# GPM8F3496A.net
KiCad netlist of a schematic drawn in Altium Designer
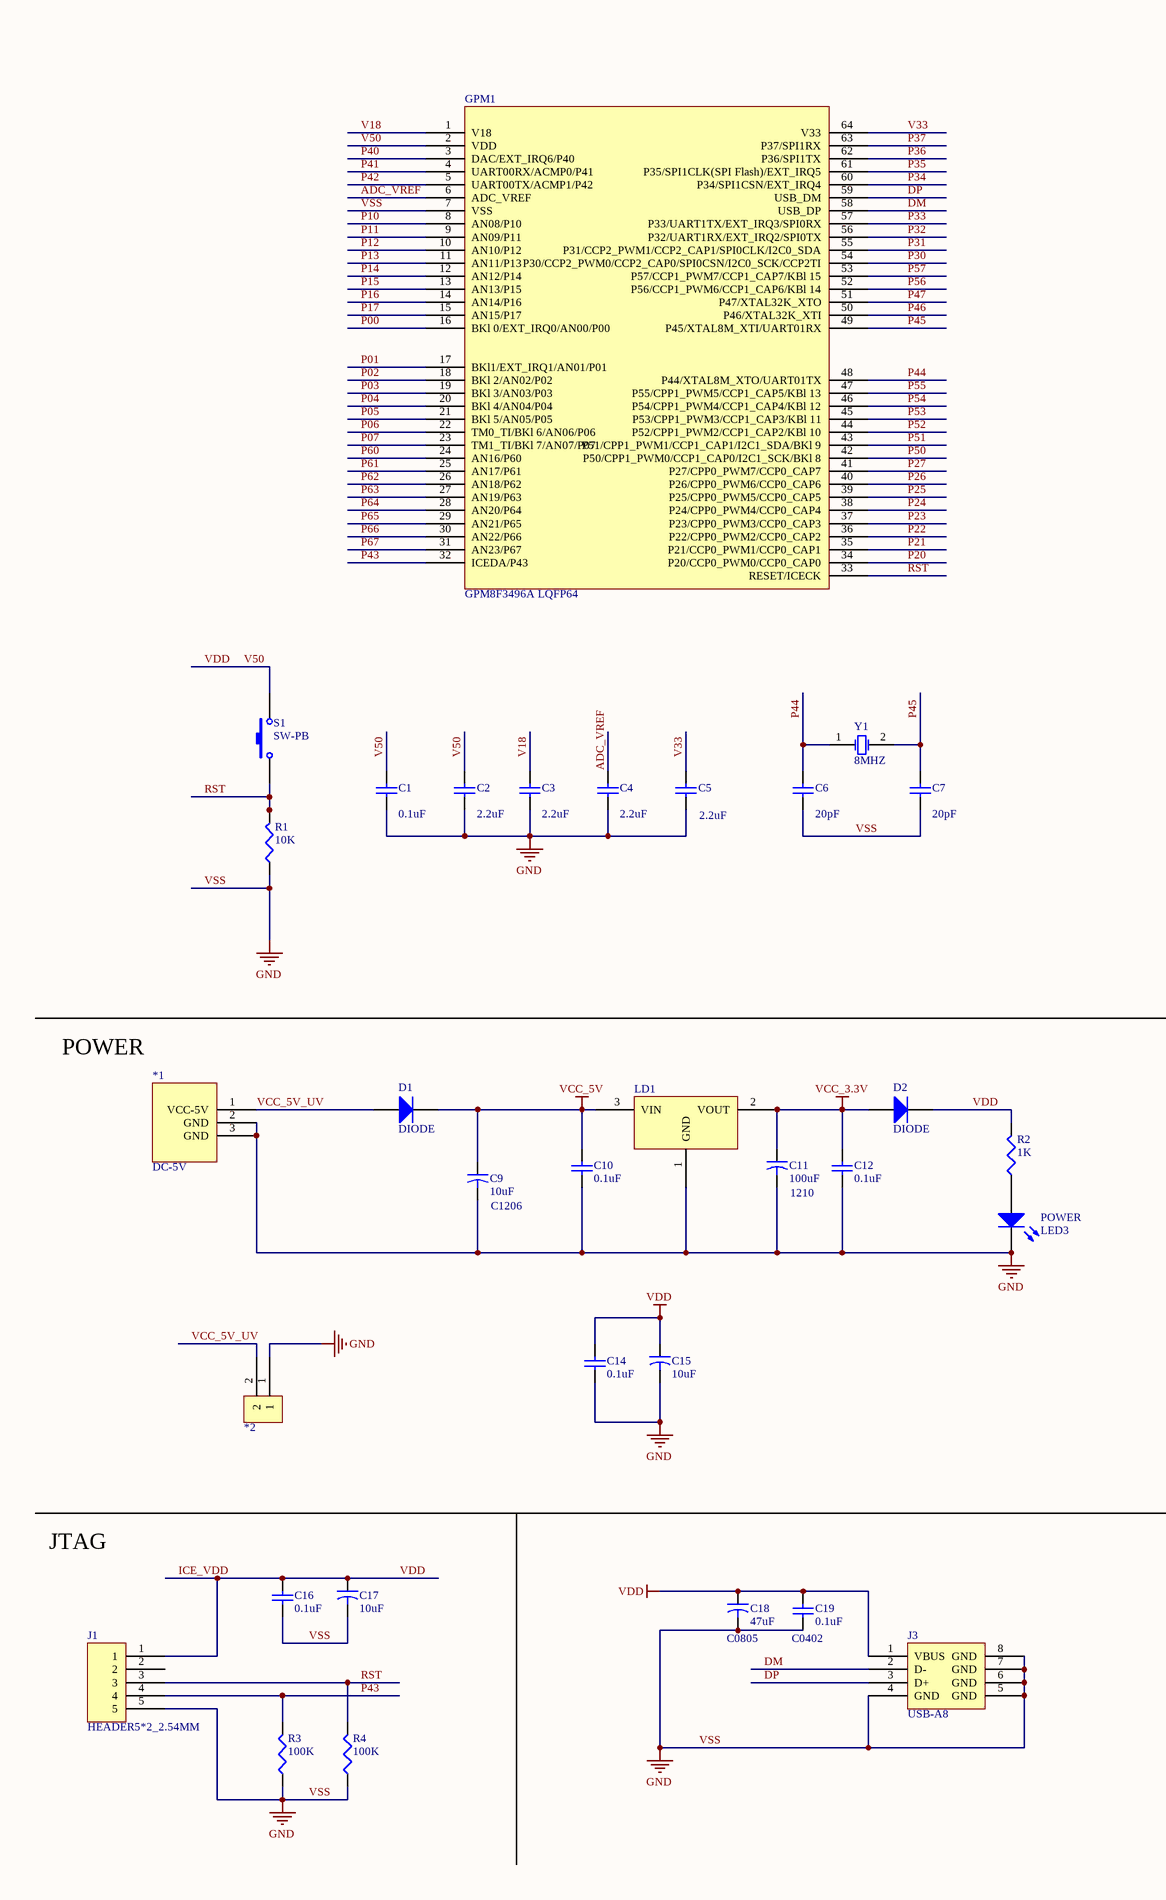
[diagram p0: GPM8F3496A.SchDoc, left]
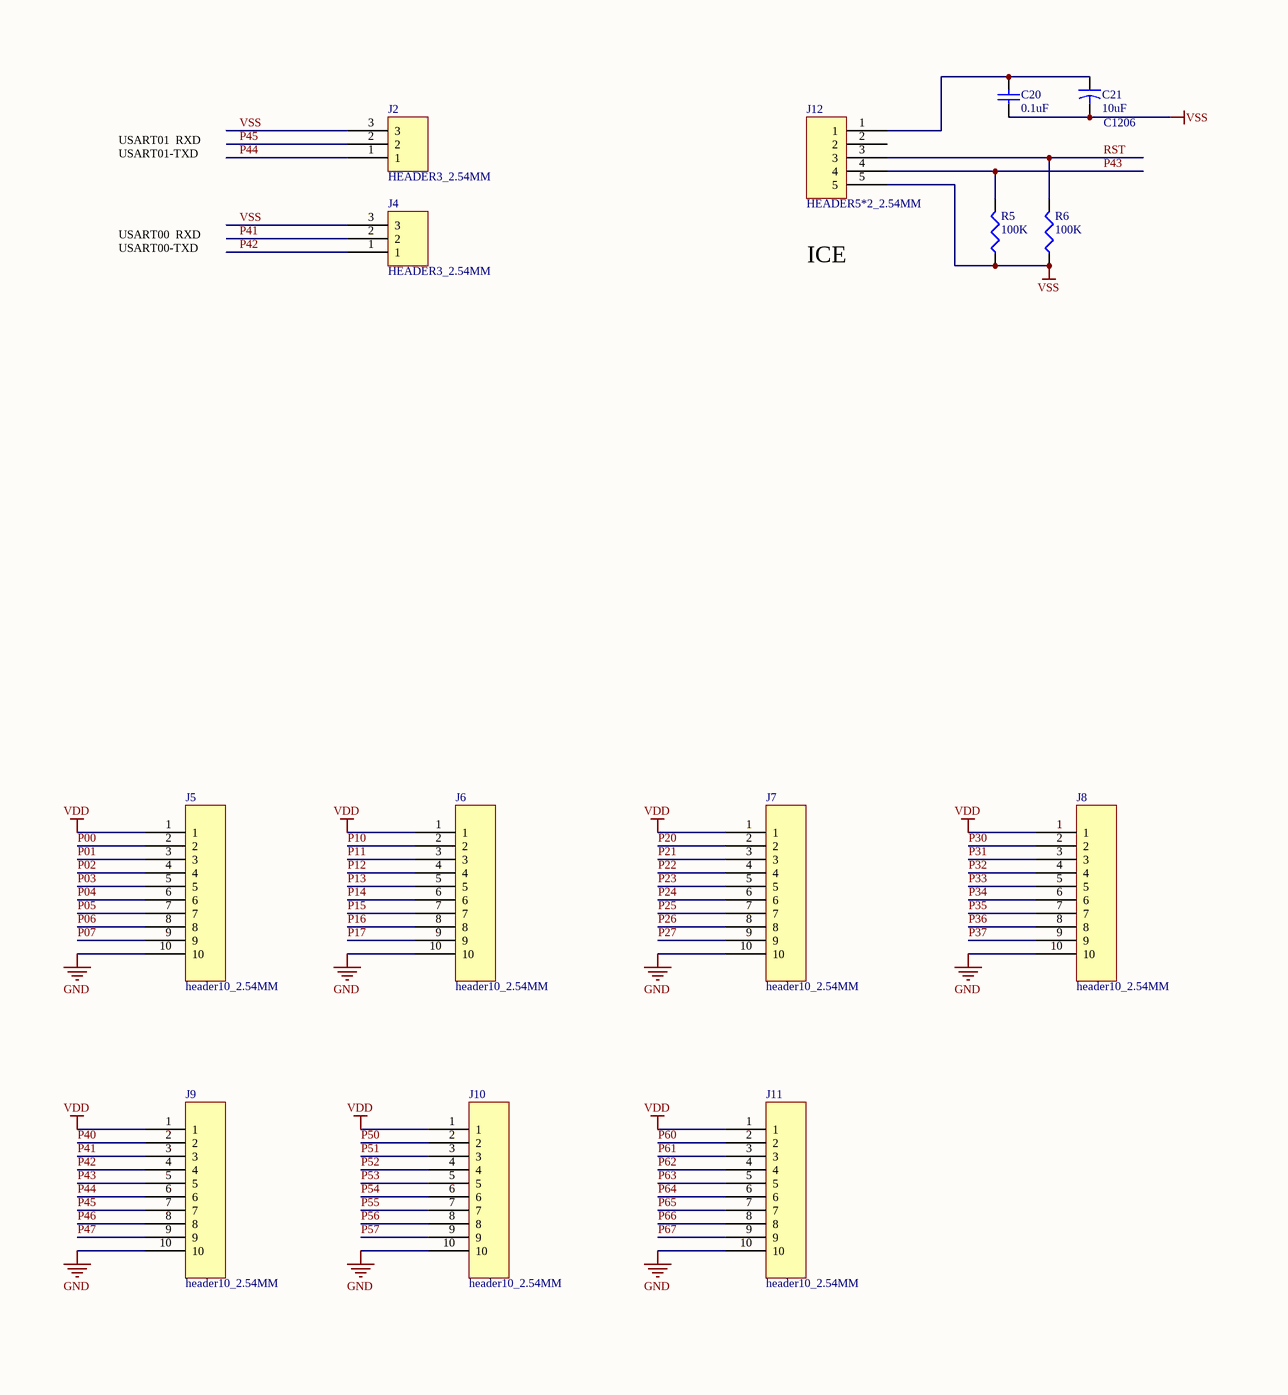
[diagram p1: GPM8F3496A.SchDoc, right]

(export (version "E")
  (design (tool "Eeschema 10.0.6"))
  (components
    (comp (ref "*1")
      (value "DC-5V")
      (footprint "DC-5V")
      (libsource (lib "Integrated_Library") (part "DC-5V"))
    )
    (comp (ref "*2")
      (value "2PIN_PITCH_2.54MM")
      (footprint "2PIN_PITCH_2.54MM")
      (libsource (lib "Integrated_Library") (part "2PIN_PITCH_2.54MM"))
    )
    (comp (ref "C1")
      (value "0.1uF")
      (footprint "C0402")
      (description "Capacitor")
      (fields (field (name "Comment") "Cap") (field (name "PUBLISHER") "Altium Limited"))
      (libsource (lib "Miscellaneous Devices") (part "Cap"))
    )
    (comp (ref "C2")
      (value "2.2uF")
      (footprint "C0402")
      (description "Capacitor")
      (fields (field (name "Comment") "Cap") (field (name "PUBLISHER") "Altium Limited"))
      (libsource (lib "Miscellaneous Devices") (part "Cap"))
    )
    (comp (ref "C3")
      (value "2.2uF")
      (footprint "C0402")
      (description "Capacitor")
      (fields (field (name "Comment") "Cap") (field (name "PUBLISHER") "Altium Limited"))
      (libsource (lib "Miscellaneous Devices") (part "Cap"))
    )
    (comp (ref "C4")
      (value "2.2uF")
      (footprint "C0402")
      (description "Capacitor")
      (fields (field (name "Comment") "Cap") (field (name "PUBLISHER") "Altium Limited"))
      (libsource (lib "Miscellaneous Devices") (part "Cap"))
    )
    (comp (ref "C5")
      (value "2.2uF")
      (footprint "C0402")
      (description "Capacitor")
      (fields (field (name "PUBLISHER") "Altium Limited"))
      (libsource (lib "Miscellaneous Devices") (part "Cap"))
    )
    (comp (ref "C6")
      (value "20pF")
      (footprint "C0402")
      (description "Capacitor")
      (fields (field (name "Comment") "Cap") (field (name "PUBLISHER") "Altium Limited"))
      (libsource (lib "Miscellaneous Devices") (part "Cap"))
    )
    (comp (ref "C7")
      (value "20pF")
      (footprint "C0402")
      (description "Capacitor")
      (fields (field (name "Comment") "Cap") (field (name "PUBLISHER") "Altium Limited"))
      (libsource (lib "Miscellaneous Devices") (part "Cap"))
    )
    (comp (ref "C9")
      (value "10uF")
      (footprint "C1206")
      (description "Capacitor")
      (fields (field (name "PUBLISHER") "Altium Limited"))
      (libsource (lib "Miscellaneous Devices") (part "Cap2"))
    )
    (comp (ref "C10")
      (value "0.1uF")
      (footprint "C0402")
      (description "Capacitor")
      (fields (field (name "PUBLISHER") "Altium Limited"))
      (libsource (lib "Miscellaneous Devices") (part "Cap"))
    )
    (comp (ref "C11")
      (value "100uF")
      (footprint "1210")
      (description "Capacitor")
      (fields (field (name "PUBLISHER") "Altium Limited"))
      (libsource (lib "Miscellaneous Devices") (part "Cap2"))
    )
    (comp (ref "C12")
      (value "0.1uF")
      (footprint "C0402")
      (description "Capacitor")
      (fields (field (name "PUBLISHER") "Altium Limited"))
      (libsource (lib "Miscellaneous Devices") (part "Cap"))
    )
    (comp (ref "C14")
      (value "0.1uF")
      (footprint "C0402")
      (description "Capacitor")
      (fields (field (name "PUBLISHER") "Altium Limited"))
      (libsource (lib "Miscellaneous Devices") (part "Cap"))
    )
    (comp (ref "C15")
      (value "10uF")
      (footprint "C1206")
      (description "Capacitor")
      (fields (field (name "PUBLISHER") "Altium Limited"))
      (libsource (lib "Miscellaneous Devices") (part "Cap2"))
    )
    (comp (ref "C16")
      (value "0.1uF")
      (footprint "C0402")
      (description "Capacitor")
      (fields (field (name "PUBLISHER") "Altium Limited"))
      (libsource (lib "Miscellaneous Devices") (part "Cap"))
    )
    (comp (ref "C17")
      (value "10uF")
      (footprint "C1206")
      (description "Capacitor")
      (fields (field (name "PUBLISHER") "Altium Limited"))
      (libsource (lib "Miscellaneous Devices") (part "Cap2"))
    )
    (comp (ref "C18")
      (value "47uF")
      (footprint "C0805")
      (description "Capacitor")
      (fields (field (name "PUBLISHER") "Altium Limited"))
      (libsource (lib "Miscellaneous Devices") (part "Cap2"))
    )
    (comp (ref "C19")
      (value "0.1uF")
      (footprint "C0402")
      (description "Capacitor")
      (fields (field (name "PUBLISHER") "Altium Limited"))
      (libsource (lib "Miscellaneous Devices") (part "Cap"))
    )
    (comp (ref "C20")
      (value "0.1uF")
      (footprint "C0402")
      (description "Capacitor")
      (fields (field (name "PUBLISHER") "Altium Limited"))
      (libsource (lib "Miscellaneous Devices") (part "Cap"))
    )
    (comp (ref "C21")
      (value "10uF")
      (footprint "C1206")
      (description "Capacitor")
      (fields (field (name "PUBLISHER") "Altium Limited"))
      (libsource (lib "Miscellaneous Devices") (part "Cap2"))
    )
    (comp (ref "D1")
      (value "DIODE")
      (footprint "R1206")
      (description "Computer Diode")
      (fields (field (name "PUBLISHER") "Altium Limited"))
      (libsource (lib "Miscellaneous Devices") (part "Diode 1N4149"))
    )
    (comp (ref "D2")
      (value "DIODE")
      (footprint "R1206")
      (description "High Conductance Fast Diode")
      (fields (field (name "PUBLISHER") "Altium Limited"))
      (libsource (lib "Miscellaneous Devices") (part "Diode 1N914"))
    )
    (comp (ref "GPM1")
      (value "GPM8F3496A LQFP64")
      (footprint "GPM8F3496A LQFP64")
      (libsource (lib "Integrated_Library1") (part "GPM8F3496A LQFP64"))
    )
    (comp (ref "J1")
      (value "HEADER5*2_2.54MM")
      (footprint "HEADER5_2.54MM")
      (libsource (lib "Integrated_Library") (part "HEADER5*2_2.54MM"))
    )
    (comp (ref "J2")
      (value "HEADER3_2.54MM")
      (footprint "HEADER3_2.54MM")
      (libsource (lib "Integrated_Library") (part "HEADER3_2.54MM"))
    )
    (comp (ref "J3")
      (value "USB-A8")
      (footprint "USB-A8")
      (libsource (lib "Integrated_Library") (part "USB-A8"))
    )
    (comp (ref "J4")
      (value "HEADER3_2.54MM")
      (footprint "HEADER3_2.54MM")
      (libsource (lib "Integrated_Library") (part "HEADER3_2.54MM"))
    )
    (comp (ref "J5")
      (value "header10_2.54MM")
      (footprint "HEADER10_2.54MM")
      (libsource (lib "Integrated_Library") (part "header10_2.54MM"))
    )
    (comp (ref "J6")
      (value "header10_2.54MM")
      (footprint "HEADER10_2.54MM")
      (libsource (lib "Integrated_Library") (part "header10_2.54MM"))
    )
    (comp (ref "J7")
      (value "header10_2.54MM")
      (footprint "HEADER10_2.54MM")
      (libsource (lib "Integrated_Library") (part "header10_2.54MM"))
    )
    (comp (ref "J8")
      (value "header10_2.54MM")
      (footprint "HEADER10_2.54MM")
      (libsource (lib "Integrated_Library") (part "header10_2.54MM"))
    )
    (comp (ref "J9")
      (value "header10_2.54MM")
      (footprint "HEADER10_2.54MM")
      (libsource (lib "Integrated_Library") (part "header10_2.54MM"))
    )
    (comp (ref "J10")
      (value "header10_2.54MM")
      (footprint "HEADER10_2.54MM")
      (libsource (lib "Integrated_Library") (part "header10_2.54MM"))
    )
    (comp (ref "J11")
      (value "header10_2.54MM")
      (footprint "HEADER10_2.54MM")
      (libsource (lib "Integrated_Library") (part "header10_2.54MM"))
    )
    (comp (ref "J12")
      (value "HEADER5*2_2.54MM")
      (footprint "HEADER5_2.54MM")
      (libsource (lib "Integrated_Library") (part "HEADER5*2_2.54MM"))
    )
    (comp (ref "LD1")
      (value "SOT-223")
      (footprint "LD1117S33TR")
      (libsource (lib "Integrated_Library") (part "LD1117S33TR"))
    )
    (comp (ref "POWER")
      (value "LED3")
      (footprint "LED_0603")
      (description "Typical BLUE SiC LED")
      (fields (field (name "PUBLISHER") "Altium Limited"))
      (libsource (lib "Miscellaneous Devices") (part "LED3"))
    )
    (comp (ref "R1")
      (value "10K")
      (footprint "R0603")
      (description "Resistor")
      (fields (field (name "PUBLISHER") "Altium Limited"))
      (libsource (lib "Miscellaneous Devices") (part "Res3"))
    )
    (comp (ref "R2")
      (value "1K")
      (footprint "R0603")
      (description "Resistor")
      (fields (field (name "PUBLISHER") "Altium Limited"))
      (libsource (lib "Miscellaneous Devices") (part "Res3"))
    )
    (comp (ref "R3")
      (value "100K")
      (footprint "R0603")
      (description "Resistor")
      (fields (field (name "PUBLISHER") "Altium Limited"))
      (libsource (lib "Miscellaneous Devices") (part "Res3"))
    )
    (comp (ref "R4")
      (value "100K")
      (footprint "R0603")
      (description "Resistor")
      (fields (field (name "PUBLISHER") "Altium Limited"))
      (libsource (lib "Miscellaneous Devices") (part "Res3"))
    )
    (comp (ref "R5")
      (value "100K")
      (footprint "R0603")
      (description "Resistor")
      (fields (field (name "PUBLISHER") "Altium Limited"))
      (libsource (lib "Miscellaneous Devices") (part "Res3"))
    )
    (comp (ref "R6")
      (value "100K")
      (footprint "R0603")
      (description "Resistor")
      (fields (field (name "PUBLISHER") "Altium Limited"))
      (libsource (lib "Miscellaneous Devices") (part "Res3"))
    )
    (comp (ref "S1")
      (value "SW-PB")
      (footprint "SWSW-2P-6.5M")
      (description "Switch")
      (fields (field (name "PUBLISHER") "Altium Limited"))
      (libsource (lib "Miscellaneous Devices") (part "SW-PB"))
    )
    (comp (ref "Y1")
      (value "8MHZ")
      (footprint "XTAL8M")
      (description "Crystal Oscillator")
      (fields (field (name "PUBLISHER") "Altium Limited"))
      (libsource (lib "Miscellaneous Devices") (part "XTAL"))
    )
  )
  (nets
    (net (code "1") (name "/ADC_VREF") (class "Default")
      (node (ref "C4") (pin "2") (pinfunction "2_2") (pintype "passive"))
      (node (ref "GPM1") (pin "6") (pinfunction "ADC_VREF_6") (pintype "passive"))
    )
    (net (code "2") (name "/DM") (class "Default")
      (node (ref "GPM1") (pin "58") (pinfunction "USB_DP_58") (pintype "passive"))
      (node (ref "J3") (pin "2") (pinfunction "D-_2") (pintype "passive"))
    )
    (net (code "3") (name "/DP") (class "Default")
      (node (ref "GPM1") (pin "59") (pinfunction "USB_DM_59") (pintype "passive"))
      (node (ref "J3") (pin "3") (pinfunction "D+_3") (pintype "passive"))
    )
    (net (code "4") (name "/P00") (class "Default")
      (node (ref "GPM1") (pin "16") (pinfunction "BKl_0/EXT_IRQ0/AN00/P00_16") (pintype "passive"))
      (node (ref "J5") (pin "2") (pinfunction "2_2") (pintype "passive"))
    )
    (net (code "5") (name "/P01") (class "Default")
      (node (ref "GPM1") (pin "17") (pinfunction "BKl1/EXT_IRQ1/AN01/P01_17") (pintype "passive"))
      (node (ref "J5") (pin "3") (pinfunction "3_3") (pintype "passive"))
    )
    (net (code "6") (name "/P02") (class "Default")
      (node (ref "GPM1") (pin "18") (pinfunction "BKl_2/AN02/P02_18") (pintype "passive"))
      (node (ref "J5") (pin "4") (pinfunction "4_4") (pintype "passive"))
    )
    (net (code "7") (name "/P03") (class "Default")
      (node (ref "GPM1") (pin "19") (pinfunction "BKl_3/AN03/P03_19") (pintype "passive"))
      (node (ref "J5") (pin "5") (pinfunction "5_5") (pintype "passive"))
    )
    (net (code "8") (name "/P04") (class "Default")
      (node (ref "GPM1") (pin "20") (pinfunction "BKl_4/AN04/P04_20") (pintype "passive"))
      (node (ref "J5") (pin "6") (pinfunction "6_6") (pintype "passive"))
    )
    (net (code "9") (name "/P05") (class "Default")
      (node (ref "GPM1") (pin "21") (pinfunction "BKl_5/AN05/P05_21") (pintype "passive"))
      (node (ref "J5") (pin "7") (pinfunction "7_7") (pintype "passive"))
    )
    (net (code "10") (name "/P06") (class "Default")
      (node (ref "GPM1") (pin "22") (pinfunction "TM0_TI/BKl_6/AN06/P06_22") (pintype "passive"))
      (node (ref "J5") (pin "8") (pinfunction "8_8") (pintype "passive"))
    )
    (net (code "11") (name "/P07") (class "Default")
      (node (ref "GPM1") (pin "23") (pinfunction "TM1_TI/BKl_7/AN07/P07_23") (pintype "passive"))
      (node (ref "J5") (pin "9") (pinfunction "9_9") (pintype "passive"))
    )
    (net (code "12") (name "/P10") (class "Default")
      (node (ref "GPM1") (pin "8") (pinfunction "AN08/P10_8") (pintype "passive"))
      (node (ref "J6") (pin "2") (pinfunction "2_2") (pintype "passive"))
    )
    (net (code "13") (name "/P11") (class "Default")
      (node (ref "GPM1") (pin "9") (pinfunction "AN09/P11_9") (pintype "passive"))
      (node (ref "J6") (pin "3") (pinfunction "3_3") (pintype "passive"))
    )
    (net (code "14") (name "/P12") (class "Default")
      (node (ref "GPM1") (pin "10") (pinfunction "AN10/P12_10") (pintype "passive"))
      (node (ref "J6") (pin "4") (pinfunction "4_4") (pintype "passive"))
    )
    (net (code "15") (name "/P13") (class "Default")
      (node (ref "GPM1") (pin "11") (pinfunction "AN11/P13_11") (pintype "passive"))
      (node (ref "J6") (pin "5") (pinfunction "5_5") (pintype "passive"))
    )
    (net (code "16") (name "/P14") (class "Default")
      (node (ref "GPM1") (pin "12") (pinfunction "AN12/P14_12") (pintype "passive"))
      (node (ref "J6") (pin "6") (pinfunction "6_6") (pintype "passive"))
    )
    (net (code "17") (name "/P15") (class "Default")
      (node (ref "GPM1") (pin "13") (pinfunction "AN13/P15_13") (pintype "passive"))
      (node (ref "J6") (pin "7") (pinfunction "7_7") (pintype "passive"))
    )
    (net (code "18") (name "/P16") (class "Default")
      (node (ref "GPM1") (pin "14") (pinfunction "AN14/P16_14") (pintype "passive"))
      (node (ref "J6") (pin "8") (pinfunction "8_8") (pintype "passive"))
    )
    (net (code "19") (name "/P17") (class "Default")
      (node (ref "GPM1") (pin "15") (pinfunction "AN15/P17_15") (pintype "passive"))
      (node (ref "J6") (pin "9") (pinfunction "9_9") (pintype "passive"))
    )
    (net (code "20") (name "/P20") (class "Default")
      (node (ref "GPM1") (pin "34") (pinfunction "P20/CCP0_PWM0/CCP0_CAP0_34") (pintype "passive"))
      (node (ref "J7") (pin "2") (pinfunction "2_2") (pintype "passive"))
    )
    (net (code "21") (name "/P21") (class "Default")
      (node (ref "GPM1") (pin "35") (pinfunction "P21/CCP0_PWM1/CCP0_CAP1_35") (pintype "passive"))
      (node (ref "J7") (pin "3") (pinfunction "3_3") (pintype "passive"))
    )
    (net (code "22") (name "/P22") (class "Default")
      (node (ref "GPM1") (pin "36") (pinfunction "P22/CPP0_PWM2/CCP0_CAP2_36") (pintype "passive"))
      (node (ref "J7") (pin "4") (pinfunction "4_4") (pintype "passive"))
    )
    (net (code "23") (name "/P23") (class "Default")
      (node (ref "GPM1") (pin "37") (pinfunction "P23/CPP0_PWM3/CCP0_CAP3_37") (pintype "passive"))
      (node (ref "J7") (pin "5") (pinfunction "5_5") (pintype "passive"))
    )
    (net (code "24") (name "/P24") (class "Default")
      (node (ref "GPM1") (pin "38") (pinfunction "P24/CPP0_PWM4/CCP0_CAP4_38") (pintype "passive"))
      (node (ref "J7") (pin "6") (pinfunction "6_6") (pintype "passive"))
    )
    (net (code "25") (name "/P25") (class "Default")
      (node (ref "GPM1") (pin "39") (pinfunction "P25/CPP0_PWM5/CCP0_CAP5_39") (pintype "passive"))
      (node (ref "J7") (pin "7") (pinfunction "7_7") (pintype "passive"))
    )
    (net (code "26") (name "/P26") (class "Default")
      (node (ref "GPM1") (pin "40") (pinfunction "P26/CPP0_PWM6/CCP0_CAP6_40") (pintype "passive"))
      (node (ref "J7") (pin "8") (pinfunction "8_8") (pintype "passive"))
    )
    (net (code "27") (name "/P27") (class "Default")
      (node (ref "GPM1") (pin "41") (pinfunction "P27/CPP0_PWM7/CCP0_CAP7_41") (pintype "passive"))
      (node (ref "J7") (pin "9") (pinfunction "9_9") (pintype "passive"))
    )
    (net (code "28") (name "/P30") (class "Default")
      (node (ref "GPM1") (pin "54") (pinfunction "P30/CCP2_PWM0/CCP2_CAP0/SPI0CSN/I2C0_SCK/CCP2TI_54") (pintype "passive"))
      (node (ref "J8") (pin "2") (pinfunction "2_2") (pintype "passive"))
    )
    (net (code "29") (name "/P31") (class "Default")
      (node (ref "GPM1") (pin "55") (pinfunction "P31/CCP2_PWM1/CCP2_CAP1/SPI0CLK/I2C0_SDA_55") (pintype "passive"))
      (node (ref "J8") (pin "3") (pinfunction "3_3") (pintype "passive"))
    )
    (net (code "30") (name "/P32") (class "Default")
      (node (ref "GPM1") (pin "56") (pinfunction "P32/UART1RX/EXT_IRQ2/SPI0TX_56") (pintype "passive"))
      (node (ref "J8") (pin "4") (pinfunction "4_4") (pintype "passive"))
    )
    (net (code "31") (name "/P33") (class "Default")
      (node (ref "GPM1") (pin "57") (pinfunction "P33/UART1TX/EXT_IRQ3/SPI0RX_57") (pintype "passive"))
      (node (ref "J8") (pin "5") (pinfunction "5_5") (pintype "passive"))
    )
    (net (code "32") (name "/P34") (class "Default")
      (node (ref "GPM1") (pin "60") (pinfunction "P34/SPI1CSN/EXT_IRQ4_60") (pintype "passive"))
      (node (ref "J8") (pin "6") (pinfunction "6_6") (pintype "passive"))
    )
    (net (code "33") (name "/P35") (class "Default")
      (node (ref "GPM1") (pin "61") (pinfunction "P35/SPI1CLK(SPI_Flash)/EXT_IRQ5_61") (pintype "passive"))
      (node (ref "J8") (pin "7") (pinfunction "7_7") (pintype "passive"))
    )
    (net (code "34") (name "/P36") (class "Default")
      (node (ref "GPM1") (pin "62") (pinfunction "P36/SPI1TX_62") (pintype "passive"))
      (node (ref "J8") (pin "8") (pinfunction "8_8") (pintype "passive"))
    )
    (net (code "35") (name "/P37") (class "Default")
      (node (ref "GPM1") (pin "63") (pinfunction "P37/SPI1RX_63") (pintype "passive"))
      (node (ref "J8") (pin "9") (pinfunction "9_9") (pintype "passive"))
    )
    (net (code "36") (name "/P40") (class "Default")
      (node (ref "GPM1") (pin "3") (pinfunction "DAC/EXT_IRQ6/P40_3") (pintype "passive"))
      (node (ref "J9") (pin "2") (pinfunction "2_2") (pintype "passive"))
    )
    (net (code "37") (name "/P41") (class "Default")
      (node (ref "GPM1") (pin "4") (pinfunction "UART00RX/ACMP0/P41_4") (pintype "passive"))
      (node (ref "J4") (pin "2") (pinfunction "2_2") (pintype "passive"))
      (node (ref "J9") (pin "3") (pinfunction "3_3") (pintype "passive"))
    )
    (net (code "38") (name "/P42") (class "Default")
      (node (ref "GPM1") (pin "5") (pinfunction "UART00TX/ACMP1/P42_5") (pintype "passive"))
      (node (ref "J4") (pin "1") (pinfunction "1_1") (pintype "passive"))
      (node (ref "J9") (pin "4") (pinfunction "4_4") (pintype "passive"))
    )
    (net (code "39") (name "/P43") (class "Default")
      (node (ref "GPM1") (pin "32") (pinfunction "ICEDA/P43_32") (pintype "passive"))
      (node (ref "J1") (pin "4") (pinfunction "4_4") (pintype "passive"))
      (node (ref "J12") (pin "4") (pinfunction "4_4") (pintype "passive"))
      (node (ref "J9") (pin "5") (pinfunction "5_5") (pintype "passive"))
      (node (ref "R3") (pin "2") (pinfunction "2_2") (pintype "passive"))
      (node (ref "R5") (pin "2") (pinfunction "2_2") (pintype "passive"))
    )
    (net (code "40") (name "/P44") (class "Default")
      (node (ref "C6") (pin "2") (pinfunction "2_2") (pintype "passive"))
      (node (ref "GPM1") (pin "48") (pinfunction "P44/XTAL8M_XTO/UART01TX_48") (pintype "passive"))
      (node (ref "J2") (pin "1") (pinfunction "1_1") (pintype "passive"))
      (node (ref "J9") (pin "6") (pinfunction "6_6") (pintype "passive"))
      (node (ref "Y1") (pin "1") (pinfunction "OSC1_1") (pintype "passive"))
    )
    (net (code "41") (name "/P45") (class "Default")
      (node (ref "C7") (pin "2") (pinfunction "2_2") (pintype "passive"))
      (node (ref "GPM1") (pin "49") (pinfunction "P45/XTAL8M_XTI/UART01RX_49") (pintype "passive"))
      (node (ref "J2") (pin "2") (pinfunction "2_2") (pintype "passive"))
      (node (ref "J9") (pin "7") (pinfunction "7_7") (pintype "passive"))
      (node (ref "Y1") (pin "2") (pinfunction "OSC2_2") (pintype "passive"))
    )
    (net (code "42") (name "/P46") (class "Default")
      (node (ref "GPM1") (pin "50") (pinfunction "P46/XTAL32K_XTI_50") (pintype "passive"))
      (node (ref "J9") (pin "8") (pinfunction "8_8") (pintype "passive"))
    )
    (net (code "43") (name "/P47") (class "Default")
      (node (ref "GPM1") (pin "51") (pinfunction "P47/XTAL32K_XTO_51") (pintype "passive"))
      (node (ref "J9") (pin "9") (pinfunction "9_9") (pintype "passive"))
    )
    (net (code "44") (name "/P50") (class "Default")
      (node (ref "GPM1") (pin "42") (pinfunction "P50/CPP1_PWM0/CCP1_CAP0/I2C1_SCK/BKl_8_42") (pintype "passive"))
      (node (ref "J10") (pin "2") (pinfunction "2_2") (pintype "passive"))
    )
    (net (code "45") (name "/P51") (class "Default")
      (node (ref "GPM1") (pin "43") (pinfunction "P51/CPP1_PWM1/CCP1_CAP1/I2C1_SDA/BKl_9_43") (pintype "passive"))
      (node (ref "J10") (pin "3") (pinfunction "3_3") (pintype "passive"))
    )
    (net (code "46") (name "/P52") (class "Default")
      (node (ref "GPM1") (pin "44") (pinfunction "P52/CPP1_PWM2/CCP1_CAP2/KBl_10_44") (pintype "passive"))
      (node (ref "J10") (pin "4") (pinfunction "4_4") (pintype "passive"))
    )
    (net (code "47") (name "/P53") (class "Default")
      (node (ref "GPM1") (pin "45") (pinfunction "P53/CPP1_PWM3/CCP1_CAP3/KBl_11_45") (pintype "passive"))
      (node (ref "J10") (pin "5") (pinfunction "5_5") (pintype "passive"))
    )
    (net (code "48") (name "/P54") (class "Default")
      (node (ref "GPM1") (pin "46") (pinfunction "P54/CPP1_PWM4/CCP1_CAP4/KBl_12_46") (pintype "passive"))
      (node (ref "J10") (pin "6") (pinfunction "6_6") (pintype "passive"))
    )
    (net (code "49") (name "/P55") (class "Default")
      (node (ref "GPM1") (pin "47") (pinfunction "P55/CPP1_PWM5/CCP1_CAP5/KBl_13_47") (pintype "passive"))
      (node (ref "J10") (pin "7") (pinfunction "7_7") (pintype "passive"))
    )
    (net (code "50") (name "/P56") (class "Default")
      (node (ref "GPM1") (pin "52") (pinfunction "P56/CCP1_PWM6/CCP1_CAP6/KBl_14_52") (pintype "passive"))
      (node (ref "J10") (pin "8") (pinfunction "8_8") (pintype "passive"))
    )
    (net (code "51") (name "/P57") (class "Default")
      (node (ref "GPM1") (pin "53") (pinfunction "P57/CCP1_PWM7/CCP1_CAP7/KBl_15_53") (pintype "passive"))
      (node (ref "J10") (pin "9") (pinfunction "9_9") (pintype "passive"))
    )
    (net (code "52") (name "/P60") (class "Default")
      (node (ref "GPM1") (pin "24") (pinfunction "AN16/P60_24") (pintype "passive"))
      (node (ref "J11") (pin "2") (pinfunction "2_2") (pintype "passive"))
    )
    (net (code "53") (name "/P61") (class "Default")
      (node (ref "GPM1") (pin "25") (pinfunction "AN17/P61_25") (pintype "passive"))
      (node (ref "J11") (pin "3") (pinfunction "3_3") (pintype "passive"))
    )
    (net (code "54") (name "/P62") (class "Default")
      (node (ref "GPM1") (pin "26") (pinfunction "AN18/P62_26") (pintype "passive"))
      (node (ref "J11") (pin "4") (pinfunction "4_4") (pintype "passive"))
    )
    (net (code "55") (name "/P63") (class "Default")
      (node (ref "GPM1") (pin "27") (pinfunction "AN19/P63_27") (pintype "passive"))
      (node (ref "J11") (pin "5") (pinfunction "5_5") (pintype "passive"))
    )
    (net (code "56") (name "/P64") (class "Default")
      (node (ref "GPM1") (pin "28") (pinfunction "AN20/P64_28") (pintype "passive"))
      (node (ref "J11") (pin "6") (pinfunction "6_6") (pintype "passive"))
    )
    (net (code "57") (name "/P65") (class "Default")
      (node (ref "GPM1") (pin "29") (pinfunction "AN21/P65_29") (pintype "passive"))
      (node (ref "J11") (pin "7") (pinfunction "7_7") (pintype "passive"))
    )
    (net (code "58") (name "/P66") (class "Default")
      (node (ref "GPM1") (pin "30") (pinfunction "AN22/P66_30") (pintype "passive"))
      (node (ref "J11") (pin "8") (pinfunction "8_8") (pintype "passive"))
    )
    (net (code "59") (name "/P67") (class "Default")
      (node (ref "GPM1") (pin "31") (pinfunction "AN23/P67_31") (pintype "passive"))
      (node (ref "J11") (pin "9") (pinfunction "9_9") (pintype "passive"))
    )
    (net (code "60") (name "/RST") (class "Default")
      (node (ref "GPM1") (pin "33") (pinfunction "RESET/ICECK_33") (pintype "passive"))
      (node (ref "J1") (pin "3") (pinfunction "3_3") (pintype "passive"))
      (node (ref "J12") (pin "3") (pinfunction "3_3") (pintype "passive"))
      (node (ref "R1") (pin "2") (pinfunction "2_2") (pintype "passive"))
      (node (ref "R4") (pin "2") (pinfunction "2_2") (pintype "passive"))
      (node (ref "R6") (pin "2") (pinfunction "2_2") (pintype "passive"))
      (node (ref "S1") (pin "1") (pinfunction "1_1") (pintype "passive"))
    )
    (net (code "61") (name "/V18") (class "Default")
      (node (ref "C3") (pin "2") (pinfunction "2_2") (pintype "passive"))
      (node (ref "GPM1") (pin "1") (pinfunction "V18_1") (pintype "passive"))
    )
    (net (code "62") (name "/V33") (class "Default")
      (node (ref "C5") (pin "2") (pinfunction "2_2") (pintype "passive"))
      (node (ref "GPM1") (pin "64") (pinfunction "V33_64") (pintype "passive"))
    )
    (net (code "63") (name "/VCC_5V_UV") (class "Default")
      (node (ref "*1") (pin "1") (pinfunction "VCC-5V_1") (pintype "passive"))
      (node (ref "*2") (pin "2") (pinfunction "2_2") (pintype "passive"))
      (node (ref "D1") (pin "1") (pinfunction "A_1") (pintype "passive"))
    )
    (net (code "64") (name "GND") (class "Default")
      (node (ref "*1") (pin "2") (pinfunction "GND_2") (pintype "passive"))
      (node (ref "*1") (pin "3") (pinfunction "GND_3") (pintype "passive"))
      (node (ref "*2") (pin "1") (pinfunction "1_1") (pintype "passive"))
      (node (ref "C1") (pin "1") (pinfunction "1_1") (pintype "passive"))
      (node (ref "C10") (pin "1") (pinfunction "1_1") (pintype "passive"))
      (node (ref "C11") (pin "2") (pinfunction "2_2") (pintype "passive"))
      (node (ref "C12") (pin "1") (pinfunction "1_1") (pintype "passive"))
      (node (ref "C14") (pin "1") (pinfunction "1_1") (pintype "passive"))
      (node (ref "C15") (pin "2") (pinfunction "2_2") (pintype "passive"))
      (node (ref "C16") (pin "1") (pinfunction "1_1") (pintype "passive"))
      (node (ref "C17") (pin "2") (pinfunction "2_2") (pintype "passive"))
      (node (ref "C18") (pin "2") (pinfunction "2_2") (pintype "passive"))
      (node (ref "C19") (pin "1") (pinfunction "1_1") (pintype "passive"))
      (node (ref "C2") (pin "1") (pinfunction "1_1") (pintype "passive"))
      (node (ref "C20") (pin "1") (pinfunction "1_1") (pintype "passive"))
      (node (ref "C21") (pin "2") (pinfunction "2_2") (pintype "passive"))
      (node (ref "C3") (pin "1") (pinfunction "1_1") (pintype "passive"))
      (node (ref "C4") (pin "1") (pinfunction "1_1") (pintype "passive"))
      (node (ref "C5") (pin "1") (pinfunction "1_1") (pintype "passive"))
      (node (ref "C6") (pin "1") (pinfunction "1_1") (pintype "passive"))
      (node (ref "C7") (pin "1") (pinfunction "1_1") (pintype "passive"))
      (node (ref "C9") (pin "2") (pinfunction "2_2") (pintype "passive"))
      (node (ref "GPM1") (pin "7") (pinfunction "VSS_7") (pintype "passive"))
      (node (ref "J1") (pin "5") (pinfunction "5_5") (pintype "passive"))
      (node (ref "J10") (pin "10") (pinfunction "10_10") (pintype "passive"))
      (node (ref "J11") (pin "10") (pinfunction "10_10") (pintype "passive"))
      (node (ref "J12") (pin "5") (pinfunction "5_5") (pintype "passive"))
      (node (ref "J2") (pin "3") (pinfunction "3_3") (pintype "passive"))
      (node (ref "J3") (pin "4") (pinfunction "GND_4") (pintype "passive"))
      (node (ref "J3") (pin "5") (pinfunction "GND_5") (pintype "passive"))
      (node (ref "J3") (pin "6") (pinfunction "GND_6") (pintype "passive"))
      (node (ref "J3") (pin "7") (pinfunction "GND_7") (pintype "passive"))
      (node (ref "J3") (pin "8") (pinfunction "GND_8") (pintype "passive"))
      (node (ref "J4") (pin "3") (pinfunction "3_3") (pintype "passive"))
      (node (ref "J5") (pin "10") (pinfunction "10_10") (pintype "passive"))
      (node (ref "J6") (pin "10") (pinfunction "10_10") (pintype "passive"))
      (node (ref "J7") (pin "10") (pinfunction "10_10") (pintype "passive"))
      (node (ref "J8") (pin "10") (pinfunction "10_10") (pintype "passive"))
      (node (ref "J9") (pin "10") (pinfunction "10_10") (pintype "passive"))
      (node (ref "LD1") (pin "1") (pinfunction "GND_1") (pintype "passive"))
      (node (ref "POWER") (pin "2") (pinfunction "K_2") (pintype "passive"))
      (node (ref "R1") (pin "1") (pinfunction "1_1") (pintype "passive"))
      (node (ref "R3") (pin "1") (pinfunction "1_1") (pintype "passive"))
      (node (ref "R4") (pin "1") (pinfunction "1_1") (pintype "passive"))
      (node (ref "R5") (pin "1") (pinfunction "1_1") (pintype "passive"))
      (node (ref "R6") (pin "1") (pinfunction "1_1") (pintype "passive"))
    )
    (net (code "65") (name "Net-(C20-Pad2)") (class "Default")
      (node (ref "C20") (pin "2") (pinfunction "2_2") (pintype "passive"))
      (node (ref "C21") (pin "1") (pinfunction "1_1") (pintype "passive"))
      (node (ref "J12") (pin "1") (pinfunction "1_1") (pintype "passive"))
    )
    (net (code "66") (name "Net-(POWER-A)") (class "Default")
      (node (ref "POWER") (pin "1") (pinfunction "A_1") (pintype "passive"))
      (node (ref "R2") (pin "1") (pinfunction "1_1") (pintype "passive"))
    )
    (net (code "67") (name "VCC_3.3V") (class "Default")
      (node (ref "C11") (pin "1") (pinfunction "1_1") (pintype "passive"))
      (node (ref "C12") (pin "2") (pinfunction "2_2") (pintype "passive"))
      (node (ref "D2") (pin "1") (pinfunction "A_1") (pintype "passive"))
      (node (ref "LD1") (pin "2") (pinfunction "VOUT_2") (pintype "passive"))
    )
    (net (code "68") (name "VCC_5V") (class "Default")
      (node (ref "C10") (pin "2") (pinfunction "2_2") (pintype "passive"))
      (node (ref "C9") (pin "1") (pinfunction "1_1") (pintype "passive"))
      (node (ref "D1") (pin "2") (pinfunction "K_2") (pintype "passive"))
      (node (ref "LD1") (pin "3") (pinfunction "VIN_3") (pintype "passive"))
    )
    (net (code "69") (name "VDD") (class "Default")
      (node (ref "C1") (pin "2") (pinfunction "2_2") (pintype "passive"))
      (node (ref "C14") (pin "2") (pinfunction "2_2") (pintype "passive"))
      (node (ref "C15") (pin "1") (pinfunction "1_1") (pintype "passive"))
      (node (ref "C16") (pin "2") (pinfunction "2_2") (pintype "passive"))
      (node (ref "C17") (pin "1") (pinfunction "1_1") (pintype "passive"))
      (node (ref "C18") (pin "1") (pinfunction "1_1") (pintype "passive"))
      (node (ref "C19") (pin "2") (pinfunction "2_2") (pintype "passive"))
      (node (ref "C2") (pin "2") (pinfunction "2_2") (pintype "passive"))
      (node (ref "D2") (pin "2") (pinfunction "K_2") (pintype "passive"))
      (node (ref "GPM1") (pin "2") (pinfunction "VDD_2") (pintype "passive"))
      (node (ref "J1") (pin "1") (pinfunction "1_1") (pintype "passive"))
      (node (ref "J10") (pin "1") (pinfunction "1_1") (pintype "passive"))
      (node (ref "J11") (pin "1") (pinfunction "1_1") (pintype "passive"))
      (node (ref "J3") (pin "1") (pinfunction "VBUS_1") (pintype "passive"))
      (node (ref "J5") (pin "1") (pinfunction "1_1") (pintype "passive"))
      (node (ref "J6") (pin "1") (pinfunction "1_1") (pintype "passive"))
      (node (ref "J7") (pin "1") (pinfunction "1_1") (pintype "passive"))
      (node (ref "J8") (pin "1") (pinfunction "1_1") (pintype "passive"))
      (node (ref "J9") (pin "1") (pinfunction "1_1") (pintype "passive"))
      (node (ref "R2") (pin "2") (pinfunction "2_2") (pintype "passive"))
      (node (ref "S1") (pin "2") (pinfunction "2_2") (pintype "passive"))
    )
    (net (code "70") (name "unconnected-(J1-Pad2)") (class "Default")
      (node (ref "J1") (pin "2") (pinfunction "2_2") (pintype "passive"))
    )
    (net (code "71") (name "unconnected-(J12-Pad2)") (class "Default")
      (node (ref "J12") (pin "2") (pinfunction "2_2") (pintype "passive"))
    )
  )
)
